# LCD_board.net
KiCad netlist of a schematic drawn in EAGLE
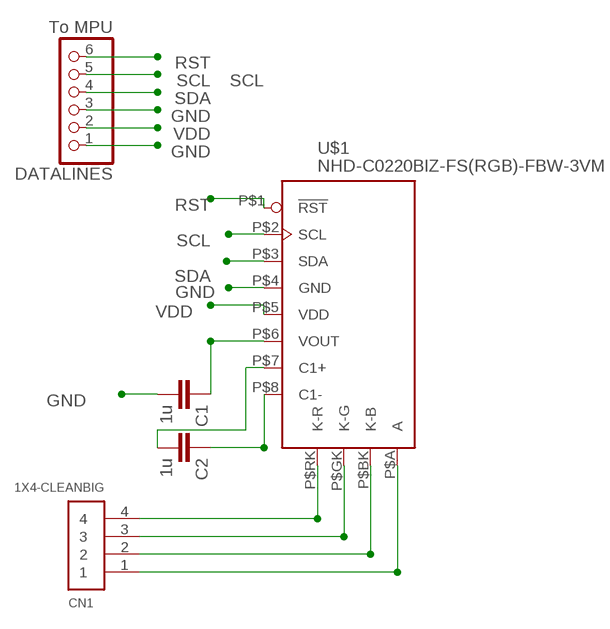
[diagram p0: schematic, sheet 1]

(export (version "E")
  (design (tool "Eeschema 10.0.6"))
  (components
    (comp (ref "C1")
      (value "1u")
      (footprint "eagle-import:C15B8")
      (libsource (lib "eagle-import") (part "C15/8"))
    )
    (comp (ref "C2")
      (value "1u")
      (footprint "eagle-import:C15B8")
      (libsource (lib "eagle-import") (part "C15/8"))
    )
    (comp (ref "CN1")
      (value "1X4-CLEANBIG")
      (footprint "eagle-import:1X04-CLEANBIG")
      (libsource (lib "eagle-import") (part "1X4-CLEANBIG"))
    )
    (comp (ref "DATALINES")
      (value "To MPU")
      (footprint "eagle-import:1X06")
      (libsource (lib "eagle-import") (part "PINHD-1X6"))
    )
    (comp (ref "U$1")
      (value "NHD-C0220BIZ-FS(RGB)-FBW-3VM")
      (footprint "eagle-import:NHD-C0220BIZ-LCD")
      (libsource (lib "eagle-import") (part "NHD-C0220BIZ-FS(RGB)-FBW-3VM"))
    )
  )
  (nets
    (net (code "1") (name "/GND") (class "Default")
      (node (ref "C1") (pin "2") (pinfunction "2_2") (pintype "passive"))
      (node (ref "DATALINES") (pin "1") (pinfunction "1_1") (pintype "passive"))
      (node (ref "DATALINES") (pin "3") (pinfunction "3_3") (pintype "passive"))
      (node (ref "U$1") (pin "P$4") (pinfunction "GND_P$4") (pintype "power_in"))
    )
    (net (code "2") (name "/RST") (class "Default")
      (node (ref "DATALINES") (pin "6") (pinfunction "6_6") (pintype "passive"))
      (node (ref "U$1") (pin "P$1") (pinfunction "~{RST}_P$1") (pintype "input"))
    )
    (net (code "3") (name "/SCL") (class "Default")
      (node (ref "DATALINES") (pin "5") (pinfunction "5_5") (pintype "passive"))
      (node (ref "U$1") (pin "P$2") (pinfunction "SCL_P$2") (pintype "bidirectional"))
    )
    (net (code "4") (name "/SDA") (class "Default")
      (node (ref "DATALINES") (pin "4") (pinfunction "4_4") (pintype "passive"))
      (node (ref "U$1") (pin "P$3") (pinfunction "SDA_P$3") (pintype "bidirectional"))
    )
    (net (code "5") (name "/VDD") (class "Default")
      (node (ref "DATALINES") (pin "2") (pinfunction "2_2") (pintype "passive"))
      (node (ref "U$1") (pin "P$5") (pinfunction "VDD_P$5") (pintype "power_in"))
    )
    (net (code "6") (name "Net-(U$1-A)") (class "Default")
      (node (ref "CN1") (pin "1") (pinfunction "1_1") (pintype "bidirectional"))
      (node (ref "U$1") (pin "P$A") (pinfunction "A_P$A") (pintype "bidirectional"))
    )
    (net (code "7") (name "Net-(U$1-C1+)") (class "Default")
      (node (ref "C2") (pin "2") (pinfunction "2_2") (pintype "passive"))
      (node (ref "U$1") (pin "P$7") (pinfunction "C1+_P$7") (pintype "bidirectional"))
    )
    (net (code "8") (name "Net-(U$1-C1-)") (class "Default")
      (node (ref "C2") (pin "1") (pinfunction "1_1") (pintype "passive"))
      (node (ref "U$1") (pin "P$8") (pinfunction "C1-_P$8") (pintype "bidirectional"))
    )
    (net (code "9") (name "Net-(U$1-K-B)") (class "Default")
      (node (ref "CN1") (pin "2") (pinfunction "2_2") (pintype "bidirectional"))
      (node (ref "U$1") (pin "P$BK") (pinfunction "K-B_P$BK") (pintype "bidirectional"))
    )
    (net (code "10") (name "Net-(U$1-K-G)") (class "Default")
      (node (ref "CN1") (pin "3") (pinfunction "3_3") (pintype "bidirectional"))
      (node (ref "U$1") (pin "P$GK") (pinfunction "K-G_P$GK") (pintype "bidirectional"))
    )
    (net (code "11") (name "Net-(U$1-K-R)") (class "Default")
      (node (ref "CN1") (pin "4") (pinfunction "4_4") (pintype "bidirectional"))
      (node (ref "U$1") (pin "P$RK") (pinfunction "K-R_P$RK") (pintype "bidirectional"))
    )
    (net (code "12") (name "Net-(U$1-VOUT)") (class "Default")
      (node (ref "C1") (pin "1") (pinfunction "1_1") (pintype "passive"))
      (node (ref "U$1") (pin "P$6") (pinfunction "VOUT_P$6") (pintype "bidirectional"))
    )
  )
)
